# proto_01.net
KiCad netlist of a schematic drawn in EAGLE
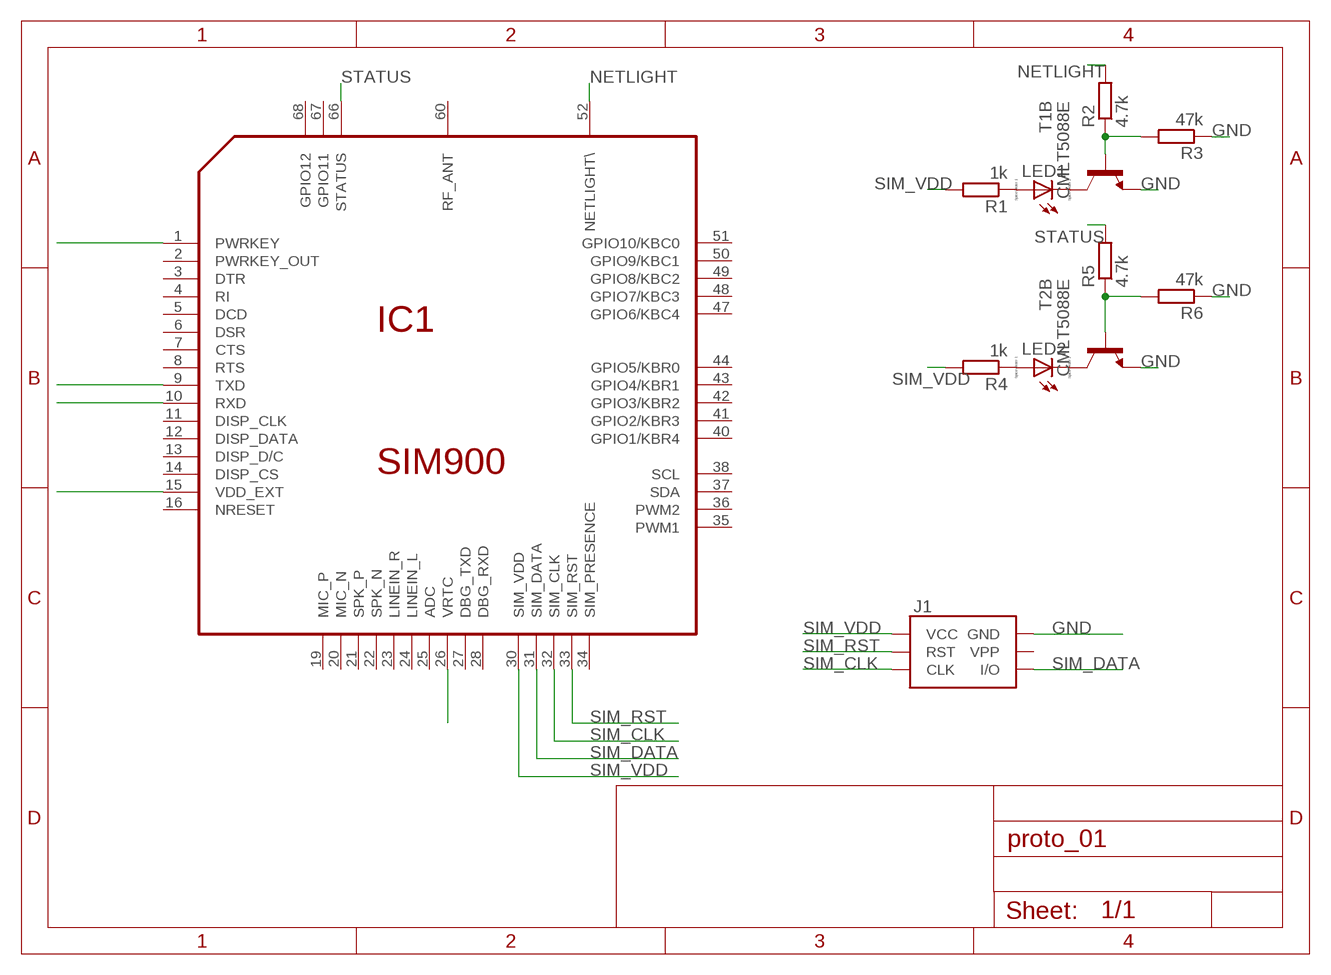
[diagram p0: schematic, sheet 1]

(export (version "E")
  (design (tool "Eeschema 10.0.6"))
  (components
    (comp (ref "IC1")
      (value "SIM900")
      (footprint "eagle-import:SIM900")
      (libsource (lib "eagle-import") (part "SIM900"))
    )
    (comp (ref "J1")
      (value "SIMHOLDERSIM")
      (footprint "eagle-import:SIMHOLDER")
      (libsource (lib "eagle-import") (part "SIMHOLDERSIM"))
    )
    (comp (ref "LED1")
      (value "LED_ESML0603")
      (footprint "eagle-import:LED_SML0603")
      (libsource (lib "eagle-import") (part "LED_ESML0603"))
    )
    (comp (ref "LED2")
      (value "LED_ESML0603")
      (footprint "eagle-import:LED_SML0603")
      (libsource (lib "eagle-import") (part "LED_ESML0603"))
    )
    (comp (ref "R1")
      (value "1k")
      (footprint "eagle-import:R0805")
      (libsource (lib "eagle-import") (part "R-EU_R0805"))
    )
    (comp (ref "R2")
      (value "4.7k")
      (footprint "eagle-import:R0805")
      (libsource (lib "eagle-import") (part "R-EU_R0805"))
    )
    (comp (ref "R3")
      (value "47k")
      (footprint "eagle-import:R0805")
      (libsource (lib "eagle-import") (part "R-EU_R0805"))
    )
    (comp (ref "R4")
      (value "1k")
      (footprint "eagle-import:R0805")
      (libsource (lib "eagle-import") (part "R-EU_R0805"))
    )
    (comp (ref "R5")
      (value "4.7k")
      (footprint "eagle-import:R0805")
      (libsource (lib "eagle-import") (part "R-EU_R0805"))
    )
    (comp (ref "R6")
      (value "47k")
      (footprint "eagle-import:R0805")
      (libsource (lib "eagle-import") (part "R-EU_R0805"))
    )
    (comp (ref "T1")
      (value "CMLT5088E")
      (footprint "eagle-import:SOT563")
      (libsource (lib "eagle-import") (part "CMLT5088E"))
    )
    (comp (ref "T2")
      (value "CMLT5088E")
      (footprint "eagle-import:SOT563")
      (libsource (lib "eagle-import") (part "CMLT5088E"))
    )
  )
  (nets
    (net (code "1") (name "/GND") (class "Default")
      (node (ref "J1") (pin "C5") (pinfunction "GND_C5") (pintype "power_in"))
      (node (ref "R3") (pin "1") (pinfunction "1_1") (pintype "passive"))
      (node (ref "R6") (pin "1") (pinfunction "1_1") (pintype "passive"))
      (node (ref "T1") (pin "4") (pinfunction "E_4") (pintype "passive"))
      (node (ref "T2") (pin "4") (pinfunction "E_4") (pintype "passive"))
    )
    (net (code "2") (name "/NETLIGHT") (class "Default")
      (node (ref "IC1") (pin "52") (pinfunction "NETLIGHT\\_52") (pintype "bidirectional"))
      (node (ref "R2") (pin "2") (pinfunction "2_2") (pintype "passive"))
    )
    (net (code "3") (name "/SIM_CLK") (class "Default")
      (node (ref "IC1") (pin "32") (pinfunction "SIM_CLK_32") (pintype "bidirectional"))
      (node (ref "J1") (pin "C3") (pinfunction "CLK_C3") (pintype "input"))
    )
    (net (code "4") (name "/SIM_DATA") (class "Default")
      (node (ref "IC1") (pin "31") (pinfunction "SIM_DATA_31") (pintype "bidirectional"))
      (node (ref "J1") (pin "C7") (pinfunction "I/O_C7") (pintype "bidirectional"))
    )
    (net (code "5") (name "/SIM_RST") (class "Default")
      (node (ref "IC1") (pin "33") (pinfunction "SIM_RST_33") (pintype "bidirectional"))
      (node (ref "J1") (pin "C2") (pinfunction "RST_C2") (pintype "input"))
    )
    (net (code "6") (name "/SIM_VDD") (class "Default")
      (node (ref "IC1") (pin "30") (pinfunction "SIM_VDD_30") (pintype "bidirectional"))
      (node (ref "J1") (pin "C1") (pinfunction "VCC_C1") (pintype "power_in"))
      (node (ref "R1") (pin "2") (pinfunction "2_2") (pintype "passive"))
      (node (ref "R4") (pin "2") (pinfunction "2_2") (pintype "passive"))
    )
    (net (code "7") (name "/STATUS") (class "Default")
      (node (ref "IC1") (pin "66") (pinfunction "STATUS_66") (pintype "bidirectional"))
      (node (ref "R5") (pin "2") (pinfunction "2_2") (pintype "passive"))
    )
    (net (code "8") (name "Net-(LED1-PadA)") (class "Default")
      (node (ref "LED1") (pin "A") (pinfunction "A_A") (pintype "passive"))
      (node (ref "R1") (pin "1") (pinfunction "1_1") (pintype "passive"))
    )
    (net (code "9") (name "Net-(LED2-PadA)") (class "Default")
      (node (ref "LED2") (pin "A") (pinfunction "A_A") (pintype "passive"))
      (node (ref "R4") (pin "1") (pinfunction "1_1") (pintype "passive"))
    )
    (net (code "10") (name "Net-(T1B-B)") (class "Default")
      (node (ref "R2") (pin "1") (pinfunction "1_1") (pintype "passive"))
      (node (ref "R3") (pin "2") (pinfunction "2_2") (pintype "passive"))
      (node (ref "T1") (pin "5") (pinfunction "B_5") (pintype "passive"))
    )
    (net (code "11") (name "Net-(T1B-C)") (class "Default")
      (node (ref "LED1") (pin "C") (pinfunction "C_C") (pintype "passive"))
      (node (ref "T1") (pin "3") (pinfunction "C_3") (pintype "passive"))
    )
    (net (code "12") (name "Net-(T2B-B)") (class "Default")
      (node (ref "R5") (pin "1") (pinfunction "1_1") (pintype "passive"))
      (node (ref "R6") (pin "2") (pinfunction "2_2") (pintype "passive"))
      (node (ref "T2") (pin "5") (pinfunction "B_5") (pintype "passive"))
    )
    (net (code "13") (name "Net-(T2B-C)") (class "Default")
      (node (ref "LED2") (pin "C") (pinfunction "C_C") (pintype "passive"))
      (node (ref "T2") (pin "3") (pinfunction "C_3") (pintype "passive"))
    )
    (net (code "14") (name "unconnected-(IC1A-ADC-Pad25)") (class "Default")
      (node (ref "IC1") (pin "25") (pinfunction "ADC_25") (pintype "bidirectional"))
    )
    (net (code "15") (name "unconnected-(IC1A-CTS-Pad7)") (class "Default")
      (node (ref "IC1") (pin "7") (pinfunction "CTS_7") (pintype "bidirectional"))
    )
    (net (code "16") (name "unconnected-(IC1A-DBG_RXD-Pad28)") (class "Default")
      (node (ref "IC1") (pin "28") (pinfunction "DBG_RXD_28") (pintype "bidirectional"))
    )
    (net (code "17") (name "unconnected-(IC1A-DBG_TXD-Pad27)") (class "Default")
      (node (ref "IC1") (pin "27") (pinfunction "DBG_TXD_27") (pintype "bidirectional"))
    )
    (net (code "18") (name "unconnected-(IC1A-DCD-Pad5)") (class "Default")
      (node (ref "IC1") (pin "5") (pinfunction "DCD_5") (pintype "bidirectional"))
    )
    (net (code "19") (name "unconnected-(IC1A-DISP_CLK-Pad11)") (class "Default")
      (node (ref "IC1") (pin "11") (pinfunction "DISP_CLK_11") (pintype "bidirectional"))
    )
    (net (code "20") (name "unconnected-(IC1A-DISP_CS-Pad14)") (class "Default")
      (node (ref "IC1") (pin "14") (pinfunction "DISP_CS_14") (pintype "bidirectional"))
    )
    (net (code "21") (name "unconnected-(IC1A-DISP_DATA-Pad12)") (class "Default")
      (node (ref "IC1") (pin "12") (pinfunction "DISP_DATA_12") (pintype "bidirectional"))
    )
    (net (code "22") (name "unconnected-(IC1A-DISP_D{slash}C-Pad13)") (class "Default")
      (node (ref "IC1") (pin "13") (pinfunction "DISP_D/C_13") (pintype "bidirectional"))
    )
    (net (code "23") (name "unconnected-(IC1A-DSR-Pad6)") (class "Default")
      (node (ref "IC1") (pin "6") (pinfunction "DSR_6") (pintype "bidirectional"))
    )
    (net (code "24") (name "unconnected-(IC1A-DTR-Pad3)") (class "Default")
      (node (ref "IC1") (pin "3") (pinfunction "DTR_3") (pintype "bidirectional"))
    )
    (net (code "25") (name "unconnected-(IC1A-GPIO1{slash}KBR4-Pad40)") (class "Default")
      (node (ref "IC1") (pin "40") (pinfunction "GPIO1/KBR4_40") (pintype "bidirectional"))
    )
    (net (code "26") (name "unconnected-(IC1A-GPIO2{slash}KBR3-Pad41)") (class "Default")
      (node (ref "IC1") (pin "41") (pinfunction "GPIO2/KBR3_41") (pintype "bidirectional"))
    )
    (net (code "27") (name "unconnected-(IC1A-GPIO3{slash}KBR2-Pad42)") (class "Default")
      (node (ref "IC1") (pin "42") (pinfunction "GPIO3/KBR2_42") (pintype "bidirectional"))
    )
    (net (code "28") (name "unconnected-(IC1A-GPIO4{slash}KBR1-Pad43)") (class "Default")
      (node (ref "IC1") (pin "43") (pinfunction "GPIO4/KBR1_43") (pintype "bidirectional"))
    )
    (net (code "29") (name "unconnected-(IC1A-GPIO5{slash}KBR0-Pad44)") (class "Default")
      (node (ref "IC1") (pin "44") (pinfunction "GPIO5/KBR0_44") (pintype "bidirectional"))
    )
    (net (code "30") (name "unconnected-(IC1A-GPIO6{slash}KBC4-Pad47)") (class "Default")
      (node (ref "IC1") (pin "47") (pinfunction "GPIO6/KBC4_47") (pintype "bidirectional"))
    )
    (net (code "31") (name "unconnected-(IC1A-GPIO7{slash}KBC3-Pad48)") (class "Default")
      (node (ref "IC1") (pin "48") (pinfunction "GPIO7/KBC3_48") (pintype "bidirectional"))
    )
    (net (code "32") (name "unconnected-(IC1A-GPIO8{slash}KBC2-Pad49)") (class "Default")
      (node (ref "IC1") (pin "49") (pinfunction "GPIO8/KBC2_49") (pintype "bidirectional"))
    )
    (net (code "33") (name "unconnected-(IC1A-GPIO9{slash}KBC1-Pad50)") (class "Default")
      (node (ref "IC1") (pin "50") (pinfunction "GPIO9/KBC1_50") (pintype "bidirectional"))
    )
    (net (code "34") (name "unconnected-(IC1A-GPIO10{slash}KBC0-Pad51)") (class "Default")
      (node (ref "IC1") (pin "51") (pinfunction "GPIO10/KBC0_51") (pintype "bidirectional"))
    )
    (net (code "35") (name "unconnected-(IC1A-GPIO11-Pad67)") (class "Default")
      (node (ref "IC1") (pin "67") (pinfunction "GPIO11_67") (pintype "bidirectional"))
    )
    (net (code "36") (name "unconnected-(IC1A-GPIO12-Pad68)") (class "Default")
      (node (ref "IC1") (pin "68") (pinfunction "GPIO12_68") (pintype "bidirectional"))
    )
    (net (code "37") (name "unconnected-(IC1A-LINEIN_L-Pad24)") (class "Default")
      (node (ref "IC1") (pin "24") (pinfunction "LINEIN_L_24") (pintype "bidirectional"))
    )
    (net (code "38") (name "unconnected-(IC1A-LINEIN_R-Pad23)") (class "Default")
      (node (ref "IC1") (pin "23") (pinfunction "LINEIN_R_23") (pintype "bidirectional"))
    )
    (net (code "39") (name "unconnected-(IC1A-MIC_N-Pad20)") (class "Default")
      (node (ref "IC1") (pin "20") (pinfunction "MIC_N_20") (pintype "bidirectional"))
    )
    (net (code "40") (name "unconnected-(IC1A-MIC_P-Pad19)") (class "Default")
      (node (ref "IC1") (pin "19") (pinfunction "MIC_P_19") (pintype "bidirectional"))
    )
    (net (code "41") (name "unconnected-(IC1A-NRESET-Pad16)") (class "Default")
      (node (ref "IC1") (pin "16") (pinfunction "NRESET_16") (pintype "bidirectional"))
    )
    (net (code "42") (name "unconnected-(IC1A-PWM1-Pad35)") (class "Default")
      (node (ref "IC1") (pin "35") (pinfunction "PWM1_35") (pintype "bidirectional"))
    )
    (net (code "43") (name "unconnected-(IC1A-PWM2-Pad36)") (class "Default")
      (node (ref "IC1") (pin "36") (pinfunction "PWM2_36") (pintype "bidirectional"))
    )
    (net (code "44") (name "unconnected-(IC1A-PWRKEY-Pad1)") (class "Default")
      (node (ref "IC1") (pin "1") (pinfunction "PWRKEY_1") (pintype "bidirectional"))
    )
    (net (code "45") (name "unconnected-(IC1A-PWRKEY_OUT-Pad2)") (class "Default")
      (node (ref "IC1") (pin "2") (pinfunction "PWRKEY_OUT_2") (pintype "bidirectional"))
    )
    (net (code "46") (name "unconnected-(IC1A-RF_ANT-Pad60)") (class "Default")
      (node (ref "IC1") (pin "60") (pinfunction "RF_ANT_60") (pintype "bidirectional"))
    )
    (net (code "47") (name "unconnected-(IC1A-RI-Pad4)") (class "Default")
      (node (ref "IC1") (pin "4") (pinfunction "RI_4") (pintype "bidirectional"))
    )
    (net (code "48") (name "unconnected-(IC1A-RTS-Pad8)") (class "Default")
      (node (ref "IC1") (pin "8") (pinfunction "RTS_8") (pintype "bidirectional"))
    )
    (net (code "49") (name "unconnected-(IC1A-RXD-Pad10)") (class "Default")
      (node (ref "IC1") (pin "10") (pinfunction "RXD_10") (pintype "bidirectional"))
    )
    (net (code "50") (name "unconnected-(IC1A-SCL-Pad38)") (class "Default")
      (node (ref "IC1") (pin "38") (pinfunction "SCL_38") (pintype "bidirectional"))
    )
    (net (code "51") (name "unconnected-(IC1A-SDA-Pad37)") (class "Default")
      (node (ref "IC1") (pin "37") (pinfunction "SDA_37") (pintype "bidirectional"))
    )
    (net (code "52") (name "unconnected-(IC1A-SIM_PRESENCE-Pad34)") (class "Default")
      (node (ref "IC1") (pin "34") (pinfunction "SIM_PRESENCE_34") (pintype "bidirectional"))
    )
    (net (code "53") (name "unconnected-(IC1A-SPK_N-Pad22)") (class "Default")
      (node (ref "IC1") (pin "22") (pinfunction "SPK_N_22") (pintype "bidirectional"))
    )
    (net (code "54") (name "unconnected-(IC1A-SPK_P-Pad21)") (class "Default")
      (node (ref "IC1") (pin "21") (pinfunction "SPK_P_21") (pintype "bidirectional"))
    )
    (net (code "55") (name "unconnected-(IC1A-TXD-Pad9)") (class "Default")
      (node (ref "IC1") (pin "9") (pinfunction "TXD_9") (pintype "bidirectional"))
    )
    (net (code "56") (name "unconnected-(IC1A-VDD_EXT-Pad15)") (class "Default")
      (node (ref "IC1") (pin "15") (pinfunction "VDD_EXT_15") (pintype "bidirectional"))
    )
    (net (code "57") (name "unconnected-(IC1A-VRTC-Pad26)") (class "Default")
      (node (ref "IC1") (pin "26") (pinfunction "VRTC_26") (pintype "bidirectional"))
    )
    (net (code "58") (name "unconnected-(J1-VPP-PadC6)") (class "Default")
      (node (ref "J1") (pin "C6") (pinfunction "VPP_C6") (pintype "input"))
    )
  )
)
